# RF_INPUT.net
KiCad netlist of a schematic drawn in EAGLE
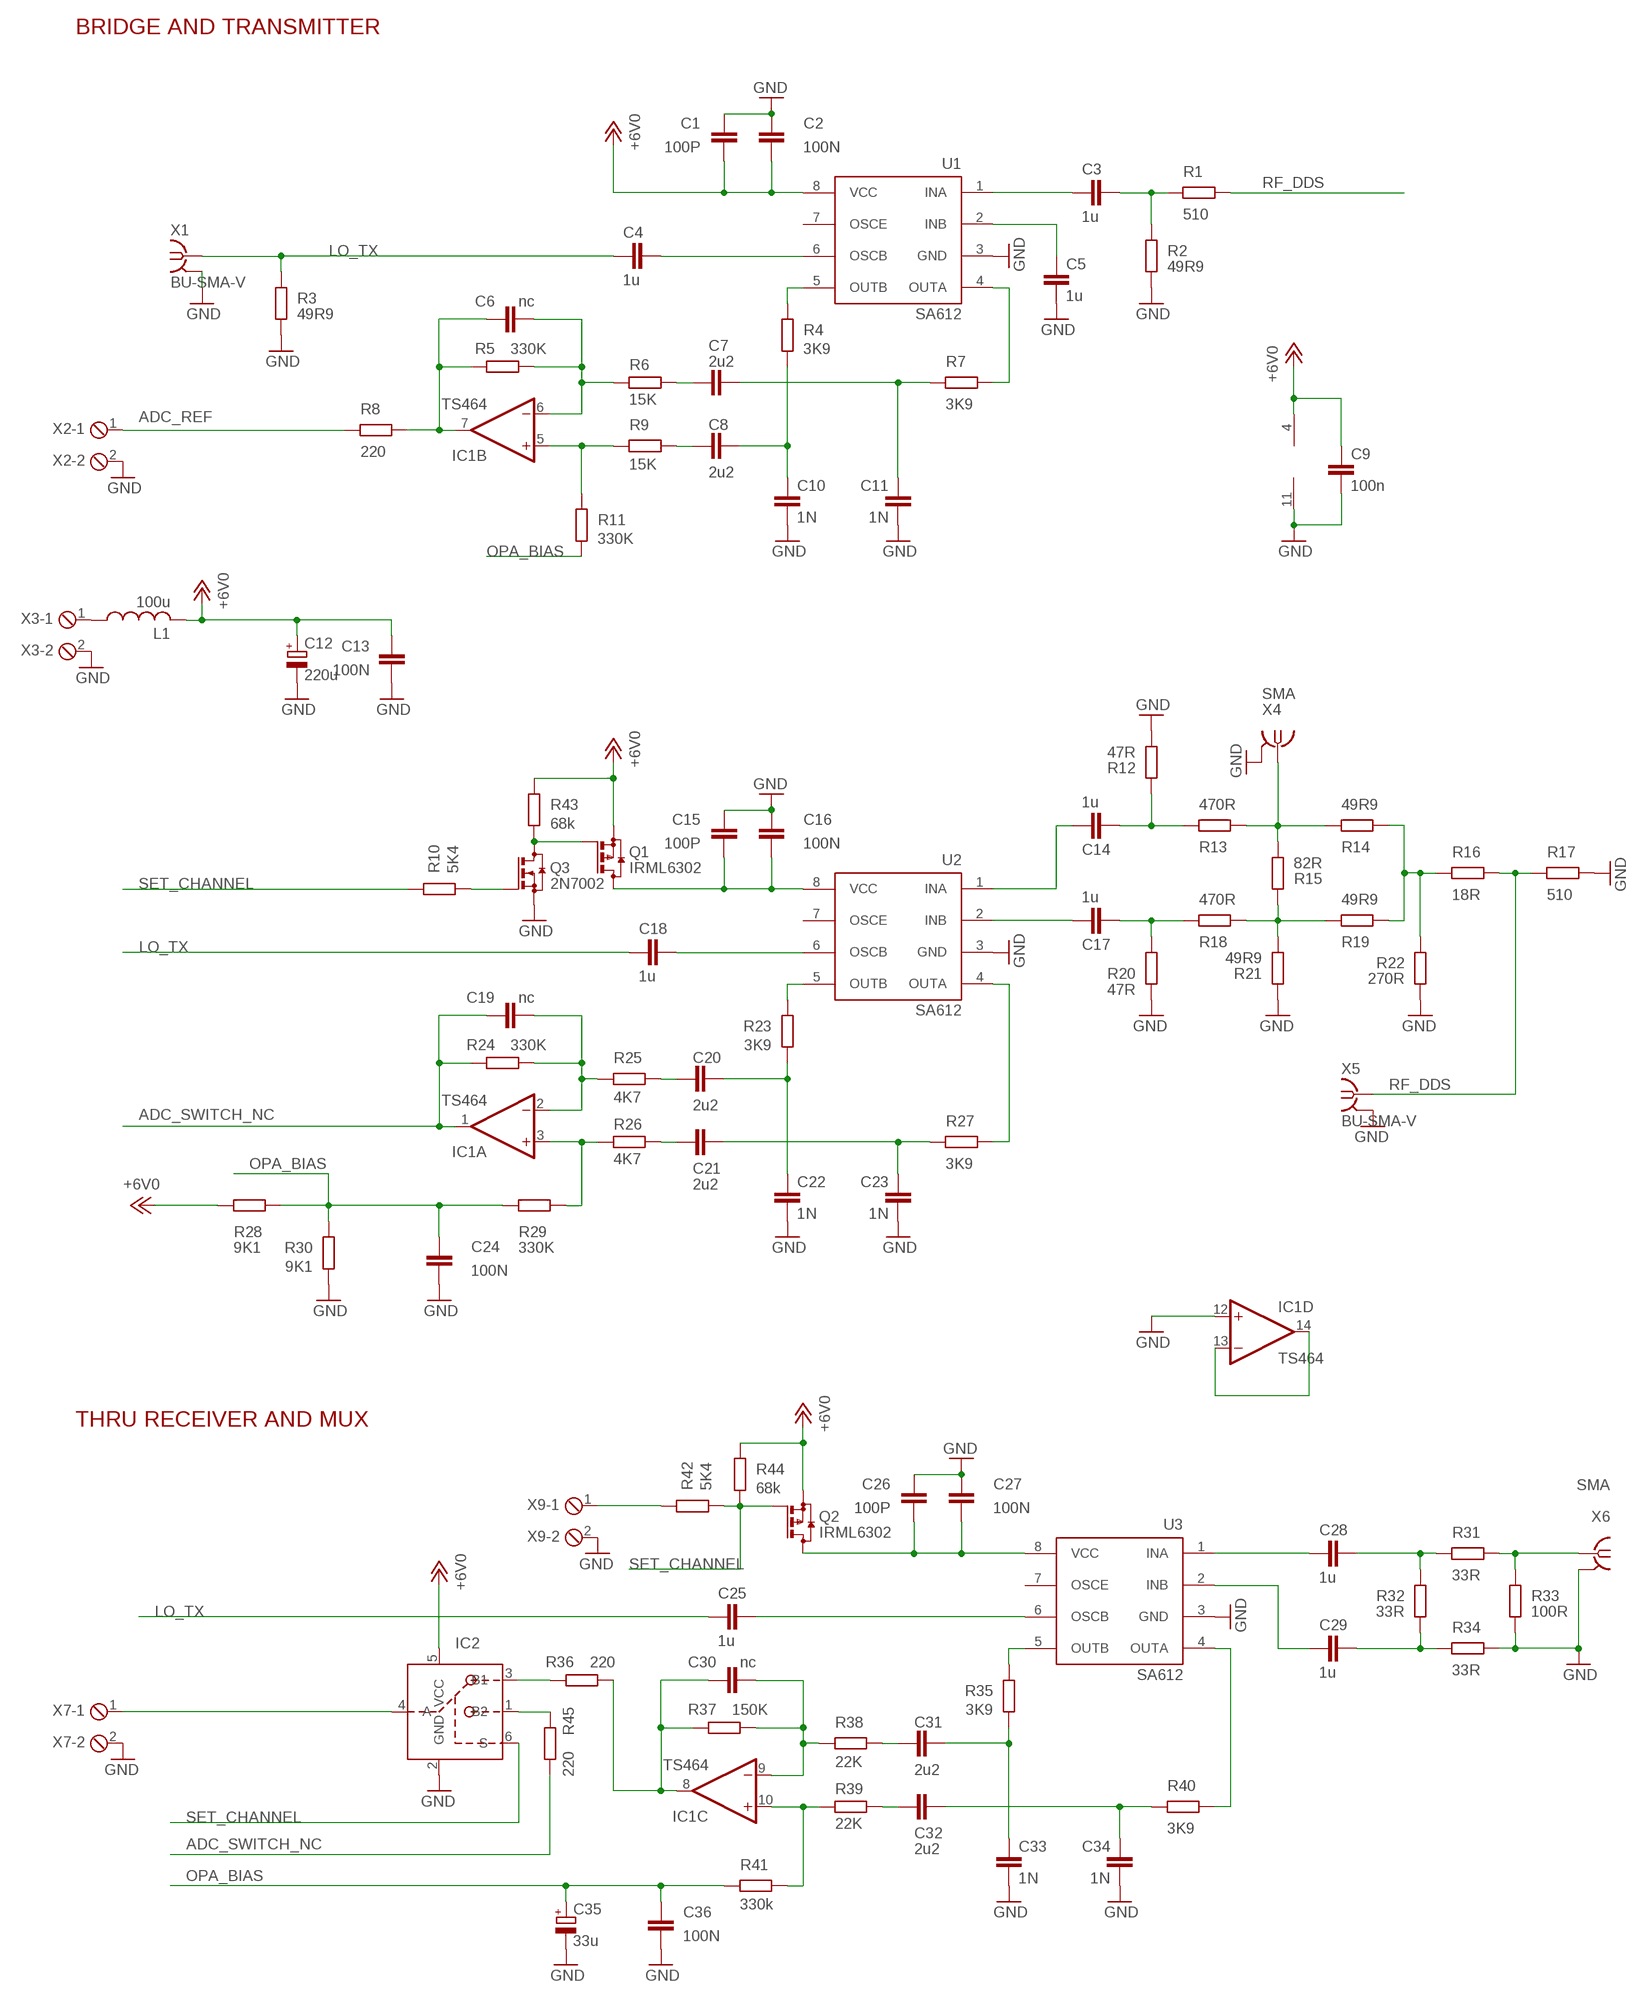
[diagram p0: schematic, sheet 1]

(export (version "E")
  (design (tool "Eeschema 10.0.6"))
  (components
    (comp (ref "C1")
      (value "100P")
      (footprint "eagle-import:C0805")
      (libsource (lib "eagle-import") (part "C-EUC0805"))
    )
    (comp (ref "C2")
      (value "100N")
      (footprint "eagle-import:C0603")
      (libsource (lib "eagle-import") (part "C-EUC0603"))
    )
    (comp (ref "C3")
      (value "1u")
      (footprint "eagle-import:C0603")
      (libsource (lib "eagle-import") (part "C-EUC0603"))
    )
    (comp (ref "C4")
      (value "1u")
      (footprint "eagle-import:C0805")
      (libsource (lib "eagle-import") (part "C-EUC0805"))
    )
    (comp (ref "C5")
      (value "1u")
      (footprint "eagle-import:C0603")
      (libsource (lib "eagle-import") (part "C-EUC0603"))
    )
    (comp (ref "C6")
      (value "nc")
      (footprint "eagle-import:C0805")
      (libsource (lib "eagle-import") (part "C-EUC0805"))
    )
    (comp (ref "C7")
      (value "2u2")
      (footprint "eagle-import:C0805")
      (libsource (lib "eagle-import") (part "C-EUC0805"))
    )
    (comp (ref "C8")
      (value "2u2")
      (footprint "eagle-import:C0805")
      (libsource (lib "eagle-import") (part "C-EUC0805"))
    )
    (comp (ref "C9")
      (value "100n")
      (footprint "eagle-import:C0603")
      (libsource (lib "eagle-import") (part "C-EUC0603"))
    )
    (comp (ref "C10")
      (value "1N")
      (footprint "eagle-import:C0805")
      (libsource (lib "eagle-import") (part "C-EUC0805"))
    )
    (comp (ref "C11")
      (value "1N")
      (footprint "eagle-import:C0805")
      (libsource (lib "eagle-import") (part "C-EUC0805"))
    )
    (comp (ref "C12")
      (value "220u")
      (footprint "eagle-import:153CLV-0605")
      (libsource (lib "eagle-import") (part "CPOL-EU153CLV-0605"))
    )
    (comp (ref "C13")
      (value "100N")
      (footprint "eagle-import:C0603")
      (libsource (lib "eagle-import") (part "C-EUC0603"))
    )
    (comp (ref "C14")
      (value "1u")
      (footprint "eagle-import:C0603")
      (libsource (lib "eagle-import") (part "C-EUC0603"))
    )
    (comp (ref "C15")
      (value "100P")
      (footprint "eagle-import:C0805")
      (libsource (lib "eagle-import") (part "C-EUC0805"))
    )
    (comp (ref "C16")
      (value "100N")
      (footprint "eagle-import:C0603")
      (libsource (lib "eagle-import") (part "C-EUC0603"))
    )
    (comp (ref "C17")
      (value "1u")
      (footprint "eagle-import:C0603")
      (libsource (lib "eagle-import") (part "C-EUC0603"))
    )
    (comp (ref "C18")
      (value "1u")
      (footprint "eagle-import:C0805")
      (libsource (lib "eagle-import") (part "C-EUC0805"))
    )
    (comp (ref "C19")
      (value "nc")
      (footprint "eagle-import:C0805")
      (libsource (lib "eagle-import") (part "C-EUC0805"))
    )
    (comp (ref "C20")
      (value "2u2")
      (footprint "eagle-import:C0805")
      (libsource (lib "eagle-import") (part "C-EUC0805"))
    )
    (comp (ref "C21")
      (value "2u2")
      (footprint "eagle-import:C0805")
      (libsource (lib "eagle-import") (part "C-EUC0805"))
    )
    (comp (ref "C22")
      (value "1N")
      (footprint "eagle-import:C0805")
      (libsource (lib "eagle-import") (part "C-EUC0805"))
    )
    (comp (ref "C23")
      (value "1N")
      (footprint "eagle-import:C0805")
      (libsource (lib "eagle-import") (part "C-EUC0805"))
    )
    (comp (ref "C24")
      (value "100N")
      (footprint "eagle-import:C0603")
      (libsource (lib "eagle-import") (part "C-EUC0603"))
    )
    (comp (ref "C25")
      (value "1u")
      (footprint "eagle-import:C0805")
      (libsource (lib "eagle-import") (part "C-EUC0805"))
    )
    (comp (ref "C26")
      (value "100P")
      (footprint "eagle-import:C0805")
      (libsource (lib "eagle-import") (part "C-EUC0805"))
    )
    (comp (ref "C27")
      (value "100N")
      (footprint "eagle-import:C0603")
      (libsource (lib "eagle-import") (part "C-EUC0603"))
    )
    (comp (ref "C28")
      (value "1u")
      (footprint "eagle-import:C0603")
      (libsource (lib "eagle-import") (part "C-EUC0603"))
    )
    (comp (ref "C29")
      (value "1u")
      (footprint "eagle-import:C0603")
      (libsource (lib "eagle-import") (part "C-EUC0603"))
    )
    (comp (ref "C30")
      (value "nc")
      (footprint "eagle-import:C0805")
      (libsource (lib "eagle-import") (part "C-EUC0805"))
    )
    (comp (ref "C31")
      (value "2u2")
      (footprint "eagle-import:C0805")
      (libsource (lib "eagle-import") (part "C-EUC0805"))
    )
    (comp (ref "C32")
      (value "2u2")
      (footprint "eagle-import:C0805")
      (libsource (lib "eagle-import") (part "C-EUC0805"))
    )
    (comp (ref "C33")
      (value "1N")
      (footprint "eagle-import:C0805")
      (libsource (lib "eagle-import") (part "C-EUC0805"))
    )
    (comp (ref "C34")
      (value "1N")
      (footprint "eagle-import:C0805")
      (libsource (lib "eagle-import") (part "C-EUC0805"))
    )
    (comp (ref "C35")
      (value "33u")
      (footprint "eagle-import:153CLV-0605")
      (libsource (lib "eagle-import") (part "CPOL-EU153CLV-0605"))
    )
    (comp (ref "C36")
      (value "100N")
      (footprint "eagle-import:C0603")
      (libsource (lib "eagle-import") (part "C-EUC0603"))
    )
    (comp (ref "IC1")
      (value "TS464")
      (footprint "eagle-import:SO14")
      (libsource (lib "eagle-import") (part "AD8684R"))
    )
    (comp (ref "IC2")
      (value "SN74LVC1G3157DBVR")
      (footprint "eagle-import:SOT23-6")
      (libsource (lib "eagle-import") (part "SN74LVC1G3157DBVR"))
    )
    (comp (ref "L1")
      (value "100u")
      (footprint "eagle-import:0207_12")
      (libsource (lib "eagle-import") (part "L-US0207/12"))
    )
    (comp (ref "Q1")
      (value "IRML6302")
      (footprint "eagle-import:SOT23")
      (libsource (lib "eagle-import") (part "BSS84"))
    )
    (comp (ref "Q2")
      (value "IRML6302")
      (footprint "eagle-import:SOT23")
      (libsource (lib "eagle-import") (part "BSS84"))
    )
    (comp (ref "Q3")
      (value "2N7002")
      (footprint "eagle-import:SOT23")
      (libsource (lib "eagle-import") (part "BSS123"))
    )
    (comp (ref "R1")
      (value "510")
      (footprint "eagle-import:R0603")
      (libsource (lib "eagle-import") (part "R-EU_R0603"))
    )
    (comp (ref "R2")
      (value "49R9")
      (footprint "eagle-import:R0805")
      (libsource (lib "eagle-import") (part "R-EU_R0805"))
    )
    (comp (ref "R3")
      (value "49R9")
      (footprint "eagle-import:R0805")
      (libsource (lib "eagle-import") (part "R-EU_R0805"))
    )
    (comp (ref "R4")
      (value "3K9")
      (footprint "eagle-import:R0603")
      (libsource (lib "eagle-import") (part "R-EU_R0603"))
    )
    (comp (ref "R5")
      (value "330K")
      (footprint "eagle-import:R0603")
      (libsource (lib "eagle-import") (part "R-EU_R0603"))
    )
    (comp (ref "R6")
      (value "15K")
      (footprint "eagle-import:R0603")
      (libsource (lib "eagle-import") (part "R-EU_R0603"))
    )
    (comp (ref "R7")
      (value "3K9")
      (footprint "eagle-import:R0603")
      (libsource (lib "eagle-import") (part "R-EU_R0603"))
    )
    (comp (ref "R8")
      (value "220")
      (footprint "eagle-import:R0603")
      (libsource (lib "eagle-import") (part "R-EU_R0603"))
    )
    (comp (ref "R9")
      (value "15K")
      (footprint "eagle-import:R0603")
      (libsource (lib "eagle-import") (part "R-EU_R0603"))
    )
    (comp (ref "R10")
      (value "5K4")
      (footprint "eagle-import:R0603")
      (libsource (lib "eagle-import") (part "R-EU_R0603"))
    )
    (comp (ref "R11")
      (value "330K")
      (footprint "eagle-import:R0603")
      (libsource (lib "eagle-import") (part "R-EU_R0603"))
    )
    (comp (ref "R12")
      (value "47R")
      (footprint "eagle-import:R0603")
      (libsource (lib "eagle-import") (part "R-EU_R0603"))
    )
    (comp (ref "R13")
      (value "470R")
      (footprint "eagle-import:R0603")
      (libsource (lib "eagle-import") (part "R-EU_R0603"))
    )
    (comp (ref "R14")
      (value "49R9")
      (footprint "eagle-import:R0805")
      (libsource (lib "eagle-import") (part "R-EU_R0805"))
    )
    (comp (ref "R15")
      (value "82R")
      (footprint "eagle-import:R0603")
      (libsource (lib "eagle-import") (part "R-EU_R0603"))
    )
    (comp (ref "R16")
      (value "18R")
      (footprint "eagle-import:R0603")
      (libsource (lib "eagle-import") (part "R-EU_R0603"))
    )
    (comp (ref "R17")
      (value "510")
      (footprint "eagle-import:R0603")
      (libsource (lib "eagle-import") (part "R-EU_R0603"))
    )
    (comp (ref "R18")
      (value "470R")
      (footprint "eagle-import:R0603")
      (libsource (lib "eagle-import") (part "R-EU_R0603"))
    )
    (comp (ref "R19")
      (value "49R9")
      (footprint "eagle-import:R0805")
      (libsource (lib "eagle-import") (part "R-EU_R0805"))
    )
    (comp (ref "R20")
      (value "47R")
      (footprint "eagle-import:R0603")
      (libsource (lib "eagle-import") (part "R-EU_R0603"))
    )
    (comp (ref "R21")
      (value "49R9")
      (footprint "eagle-import:R0805")
      (libsource (lib "eagle-import") (part "R-EU_R0805"))
    )
    (comp (ref "R22")
      (value "270R")
      (footprint "eagle-import:R0603")
      (libsource (lib "eagle-import") (part "R-EU_R0603"))
    )
    (comp (ref "R23")
      (value "3K9")
      (footprint "eagle-import:R0603")
      (libsource (lib "eagle-import") (part "R-EU_R0603"))
    )
    (comp (ref "R24")
      (value "330K")
      (footprint "eagle-import:R0603")
      (libsource (lib "eagle-import") (part "R-EU_R0603"))
    )
    (comp (ref "R25")
      (value "4K7")
      (footprint "eagle-import:R0603")
      (libsource (lib "eagle-import") (part "R-EU_R0603"))
    )
    (comp (ref "R26")
      (value "4K7")
      (footprint "eagle-import:R0603")
      (libsource (lib "eagle-import") (part "R-EU_R0603"))
    )
    (comp (ref "R27")
      (value "3K9")
      (footprint "eagle-import:R0603")
      (libsource (lib "eagle-import") (part "R-EU_R0603"))
    )
    (comp (ref "R28")
      (value "9K1")
      (footprint "eagle-import:R0603")
      (libsource (lib "eagle-import") (part "R-EU_R0603"))
    )
    (comp (ref "R29")
      (value "330K")
      (footprint "eagle-import:R0603")
      (libsource (lib "eagle-import") (part "R-EU_R0603"))
    )
    (comp (ref "R30")
      (value "9K1")
      (footprint "eagle-import:R0603")
      (libsource (lib "eagle-import") (part "R-EU_R0603"))
    )
    (comp (ref "R31")
      (value "33R")
      (footprint "eagle-import:R0603")
      (libsource (lib "eagle-import") (part "R-EU_R0603"))
    )
    (comp (ref "R32")
      (value "33R")
      (footprint "eagle-import:R0603")
      (libsource (lib "eagle-import") (part "R-EU_R0603"))
    )
    (comp (ref "R33")
      (value "100R")
      (footprint "eagle-import:R0603")
      (libsource (lib "eagle-import") (part "R-EU_R0603"))
    )
    (comp (ref "R34")
      (value "33R")
      (footprint "eagle-import:R0603")
      (libsource (lib "eagle-import") (part "R-EU_R0603"))
    )
    (comp (ref "R35")
      (value "3K9")
      (footprint "eagle-import:R0603")
      (libsource (lib "eagle-import") (part "R-EU_R0603"))
    )
    (comp (ref "R36")
      (value "220")
      (footprint "eagle-import:R0603")
      (libsource (lib "eagle-import") (part "R-EU_R0603"))
    )
    (comp (ref "R37")
      (value "150K")
      (footprint "eagle-import:R0603")
      (libsource (lib "eagle-import") (part "R-EU_R0603"))
    )
    (comp (ref "R38")
      (value "22K")
      (footprint "eagle-import:R0603")
      (libsource (lib "eagle-import") (part "R-EU_R0603"))
    )
    (comp (ref "R39")
      (value "22K")
      (footprint "eagle-import:R0603")
      (libsource (lib "eagle-import") (part "R-EU_R0603"))
    )
    (comp (ref "R40")
      (value "3K9")
      (footprint "eagle-import:R0603")
      (libsource (lib "eagle-import") (part "R-EU_R0603"))
    )
    (comp (ref "R41")
      (value "330k")
      (footprint "eagle-import:R0603")
      (libsource (lib "eagle-import") (part "R-EU_R0603"))
    )
    (comp (ref "R42")
      (value "5K4")
      (footprint "eagle-import:R0603")
      (libsource (lib "eagle-import") (part "R-EU_R0603"))
    )
    (comp (ref "R43")
      (value "68k")
      (footprint "eagle-import:R0603")
      (libsource (lib "eagle-import") (part "R-EU_R0603"))
    )
    (comp (ref "R44")
      (value "68k")
      (footprint "eagle-import:R0603")
      (libsource (lib "eagle-import") (part "R-EU_R0603"))
    )
    (comp (ref "R45")
      (value "220")
      (footprint "eagle-import:R0603")
      (libsource (lib "eagle-import") (part "R-EU_R0603"))
    )
    (comp (ref "U1")
      (value "SA612")
      (footprint "eagle-import:SO8")
      (libsource (lib "eagle-import") (part "SA612"))
    )
    (comp (ref "U2")
      (value "SA612")
      (footprint "eagle-import:SO8")
      (libsource (lib "eagle-import") (part "SA612"))
    )
    (comp (ref "U3")
      (value "SA612")
      (footprint "eagle-import:SO8")
      (libsource (lib "eagle-import") (part "SA612"))
    )
    (comp (ref "X1")
      (value "BU-SMA-V")
      (footprint "eagle-import:BU-SMA-V")
      (libsource (lib "eagle-import") (part "BU-SMA-V"))
    )
    (comp (ref "X2")
      (value "MPT2")
      (footprint "eagle-import:2POL254")
      (libsource (lib "eagle-import") (part "MPT2"))
    )
    (comp (ref "X3")
      (value "MPT2")
      (footprint "eagle-import:2POL254")
      (libsource (lib "eagle-import") (part "MPT2"))
    )
    (comp (ref "X4")
      (value "SMA")
      (footprint "eagle-import:J502-ND-142-0701-801_806")
      (fields (field (name "MF") "JOHNSON COMPONENTS") (field (name "MPN") "142-0701-801"))
      (libsource (lib "eagle-import") (part "SMA-142-0701-801/806"))
    )
    (comp (ref "X5")
      (value "BU-SMA-V")
      (footprint "eagle-import:BU-SMA-V")
      (libsource (lib "eagle-import") (part "BU-SMA-V"))
    )
    (comp (ref "X6")
      (value "SMA")
      (footprint "eagle-import:J502-ND-142-0701-801_806")
      (fields (field (name "MF") "JOHNSON COMPONENTS") (field (name "MPN") "142-0701-801"))
      (libsource (lib "eagle-import") (part "SMA-142-0701-801/806"))
    )
    (comp (ref "X7")
      (value "MPT2")
      (footprint "eagle-import:2POL254")
      (libsource (lib "eagle-import") (part "MPT2"))
    )
    (comp (ref "X9")
      (value "MPT2")
      (footprint "eagle-import:2POL254")
      (libsource (lib "eagle-import") (part "MPT2"))
    )
  )
  (nets
    (net (code "1") (name "+6V0") (class "Default")
      (node (ref "C1") (pin "1") (pinfunction "1_1") (pintype "passive"))
      (node (ref "C12") (pin "+") (pinfunction "+_+") (pintype "passive"))
      (node (ref "C13") (pin "1") (pinfunction "1_1") (pintype "passive"))
      (node (ref "C2") (pin "1") (pinfunction "1_1") (pintype "passive"))
      (node (ref "C9") (pin "1") (pinfunction "1_1") (pintype "passive"))
      (node (ref "IC1") (pin "4") (pinfunction "V+_4") (pintype "power_in"))
      (node (ref "IC2") (pin "5") (pinfunction "VCC_5") (pintype "power_in"))
      (node (ref "L1") (pin "2") (pinfunction "2_2") (pintype "passive"))
      (node (ref "Q1") (pin "2") (pinfunction "S_2") (pintype "passive"))
      (node (ref "Q2") (pin "2") (pinfunction "S_2") (pintype "passive"))
      (node (ref "R28") (pin "2") (pinfunction "2_2") (pintype "passive"))
      (node (ref "R43") (pin "1") (pinfunction "1_1") (pintype "passive"))
      (node (ref "R44") (pin "1") (pinfunction "1_1") (pintype "passive"))
      (node (ref "U1") (pin "8") (pinfunction "VCC_8") (pintype "bidirectional"))
    )
    (net (code "2") (name "/ADC_REF") (class "Default")
      (node (ref "R8") (pin "1") (pinfunction "1_1") (pintype "passive"))
      (node (ref "X2") (pin "1") (pinfunction "1_1") (pintype "passive"))
    )
    (net (code "3") (name "/ADC_SWITCH_NC") (class "Default")
      (node (ref "C19") (pin "1") (pinfunction "1_1") (pintype "passive"))
      (node (ref "IC1") (pin "1") (pinfunction "OUT_1") (pintype "output"))
      (node (ref "R24") (pin "2") (pinfunction "2_2") (pintype "passive"))
      (node (ref "R45") (pin "1") (pinfunction "1_1") (pintype "passive"))
    )
    (net (code "4") (name "/LO_TX") (class "Default")
      (node (ref "C18") (pin "1") (pinfunction "1_1") (pintype "passive"))
      (node (ref "C25") (pin "1") (pinfunction "1_1") (pintype "passive"))
      (node (ref "C4") (pin "1") (pinfunction "1_1") (pintype "passive"))
      (node (ref "R3") (pin "1") (pinfunction "1_1") (pintype "passive"))
      (node (ref "X1") (pin "1") (pinfunction "1_1") (pintype "passive"))
    )
    (net (code "5") (name "/OPA_BIAS") (class "Default")
      (node (ref "C24") (pin "2") (pinfunction "2_2") (pintype "passive"))
      (node (ref "C35") (pin "+") (pinfunction "+_+") (pintype "passive"))
      (node (ref "C36") (pin "1") (pinfunction "1_1") (pintype "passive"))
      (node (ref "R11") (pin "2") (pinfunction "2_2") (pintype "passive"))
      (node (ref "R28") (pin "1") (pinfunction "1_1") (pintype "passive"))
      (node (ref "R29") (pin "2") (pinfunction "2_2") (pintype "passive"))
      (node (ref "R30") (pin "1") (pinfunction "1_1") (pintype "passive"))
      (node (ref "R41") (pin "2") (pinfunction "2_2") (pintype "passive"))
    )
    (net (code "6") (name "/RF_DDS") (class "Default")
      (node (ref "R1") (pin "1") (pinfunction "1_1") (pintype "passive"))
      (node (ref "R16") (pin "1") (pinfunction "1_1") (pintype "passive"))
      (node (ref "R17") (pin "1") (pinfunction "1_1") (pintype "passive"))
      (node (ref "X5") (pin "1") (pinfunction "1_1") (pintype "passive"))
    )
    (net (code "7") (name "/SET_CHANNEL") (class "Default")
      (node (ref "IC2") (pin "6") (pinfunction "S_6") (pintype "bidirectional"))
      (node (ref "Q2") (pin "1") (pinfunction "G_1") (pintype "passive"))
      (node (ref "R10") (pin "1") (pinfunction "1_1") (pintype "passive"))
      (node (ref "R42") (pin "2") (pinfunction "2_2") (pintype "passive"))
      (node (ref "R44") (pin "2") (pinfunction "2_2") (pintype "passive"))
    )
    (net (code "8") (name "GND") (class "Default")
      (node (ref "C1") (pin "2") (pinfunction "2_2") (pintype "passive"))
      (node (ref "C10") (pin "2") (pinfunction "2_2") (pintype "passive"))
      (node (ref "C11") (pin "2") (pinfunction "2_2") (pintype "passive"))
      (node (ref "C12") (pin "-") (pinfunction "-_-") (pintype "passive"))
      (node (ref "C13") (pin "2") (pinfunction "2_2") (pintype "passive"))
      (node (ref "C15") (pin "2") (pinfunction "2_2") (pintype "passive"))
      (node (ref "C16") (pin "2") (pinfunction "2_2") (pintype "passive"))
      (node (ref "C2") (pin "2") (pinfunction "2_2") (pintype "passive"))
      (node (ref "C22") (pin "2") (pinfunction "2_2") (pintype "passive"))
      (node (ref "C23") (pin "2") (pinfunction "2_2") (pintype "passive"))
      (node (ref "C24") (pin "1") (pinfunction "1_1") (pintype "passive"))
      (node (ref "C26") (pin "2") (pinfunction "2_2") (pintype "passive"))
      (node (ref "C27") (pin "2") (pinfunction "2_2") (pintype "passive"))
      (node (ref "C33") (pin "2") (pinfunction "2_2") (pintype "passive"))
      (node (ref "C34") (pin "2") (pinfunction "2_2") (pintype "passive"))
      (node (ref "C35") (pin "-") (pinfunction "-_-") (pintype "passive"))
      (node (ref "C36") (pin "2") (pinfunction "2_2") (pintype "passive"))
      (node (ref "C5") (pin "2") (pinfunction "2_2") (pintype "passive"))
      (node (ref "C9") (pin "2") (pinfunction "2_2") (pintype "passive"))
      (node (ref "IC1") (pin "11") (pinfunction "V-_11") (pintype "power_in"))
      (node (ref "IC1") (pin "12") (pinfunction "+IN_12") (pintype "input"))
      (node (ref "IC2") (pin "2") (pinfunction "GND_2") (pintype "power_in"))
      (node (ref "Q3") (pin "2") (pinfunction "S_2") (pintype "passive"))
      (node (ref "R12") (pin "2") (pinfunction "2_2") (pintype "passive"))
      (node (ref "R17") (pin "2") (pinfunction "2_2") (pintype "passive"))
      (node (ref "R2") (pin "1") (pinfunction "1_1") (pintype "passive"))
      (node (ref "R20") (pin "1") (pinfunction "1_1") (pintype "passive"))
      (node (ref "R21") (pin "1") (pinfunction "1_1") (pintype "passive"))
      (node (ref "R22") (pin "2") (pinfunction "2_2") (pintype "passive"))
      (node (ref "R3") (pin "2") (pinfunction "2_2") (pintype "passive"))
      (node (ref "R30") (pin "2") (pinfunction "2_2") (pintype "passive"))
      (node (ref "R33") (pin "2") (pinfunction "2_2") (pintype "passive"))
      (node (ref "R34") (pin "1") (pinfunction "1_1") (pintype "passive"))
      (node (ref "U1") (pin "3") (pinfunction "GND_3") (pintype "bidirectional"))
      (node (ref "U2") (pin "3") (pinfunction "GND_3") (pintype "bidirectional"))
      (node (ref "U3") (pin "3") (pinfunction "GND_3") (pintype "bidirectional"))
      (node (ref "X1") (pin "2") (pinfunction "2_2") (pintype "passive"))
      (node (ref "X1") (pin "3") (pinfunction "2_3") (pintype "passive"))
      (node (ref "X1") (pin "4") (pinfunction "2_4") (pintype "passive"))
      (node (ref "X1") (pin "5") (pinfunction "2_5") (pintype "passive"))
      (node (ref "X2") (pin "2") (pinfunction "1_2") (pintype "passive"))
      (node (ref "X3") (pin "2") (pinfunction "1_2") (pintype "passive"))
      (node (ref "X4") (pin "G@1") (pinfunction "2_G@1") (pintype "passive"))
      (node (ref "X4") (pin "G@2") (pinfunction "2_G@2") (pintype "passive"))
      (node (ref "X4") (pin "G@3") (pinfunction "2_G@3") (pintype "passive"))
      (node (ref "X4") (pin "G@4") (pinfunction "2_G@4") (pintype "passive"))
      (node (ref "X5") (pin "2") (pinfunction "2_2") (pintype "passive"))
      (node (ref "X5") (pin "3") (pinfunction "2_3") (pintype "passive"))
      (node (ref "X5") (pin "4") (pinfunction "2_4") (pintype "passive"))
      (node (ref "X5") (pin "5") (pinfunction "2_5") (pintype "passive"))
      (node (ref "X6") (pin "G@1") (pinfunction "2_G@1") (pintype "passive"))
      (node (ref "X6") (pin "G@2") (pinfunction "2_G@2") (pintype "passive"))
      (node (ref "X6") (pin "G@3") (pinfunction "2_G@3") (pintype "passive"))
      (node (ref "X6") (pin "G@4") (pinfunction "2_G@4") (pintype "passive"))
      (node (ref "X7") (pin "2") (pinfunction "1_2") (pintype "passive"))
      (node (ref "X9") (pin "2") (pinfunction "1_2") (pintype "passive"))
    )
    (net (code "9") (name "Net-(C3-Pad2)") (class "Default")
      (node (ref "C3") (pin "2") (pinfunction "2_2") (pintype "passive"))
      (node (ref "R1") (pin "2") (pinfunction "2_2") (pintype "passive"))
      (node (ref "R2") (pin "2") (pinfunction "2_2") (pintype "passive"))
    )
    (net (code "10") (name "Net-(C7-Pad1)") (class "Default")
      (node (ref "C7") (pin "1") (pinfunction "1_1") (pintype "passive"))
      (node (ref "R6") (pin "1") (pinfunction "1_1") (pintype "passive"))
    )
    (net (code "11") (name "Net-(C8-Pad1)") (class "Default")
      (node (ref "C8") (pin "1") (pinfunction "1_1") (pintype "passive"))
      (node (ref "R9") (pin "1") (pinfunction "1_1") (pintype "passive"))
    )
    (net (code "12") (name "Net-(C10-Pad1)") (class "Default")
      (node (ref "C10") (pin "1") (pinfunction "1_1") (pintype "passive"))
      (node (ref "C8") (pin "2") (pinfunction "2_2") (pintype "passive"))
      (node (ref "R4") (pin "2") (pinfunction "2_2") (pintype "passive"))
    )
    (net (code "13") (name "Net-(C11-Pad1)") (class "Default")
      (node (ref "C11") (pin "1") (pinfunction "1_1") (pintype "passive"))
      (node (ref "C7") (pin "2") (pinfunction "2_2") (pintype "passive"))
      (node (ref "R7") (pin "2") (pinfunction "2_2") (pintype "passive"))
    )
    (net (code "14") (name "Net-(C14-Pad2)") (class "Default")
      (node (ref "C14") (pin "2") (pinfunction "2_2") (pintype "passive"))
      (node (ref "R12") (pin "1") (pinfunction "1_1") (pintype "passive"))
      (node (ref "R13") (pin "2") (pinfunction "2_2") (pintype "passive"))
    )
    (net (code "15") (name "Net-(C17-Pad2)") (class "Default")
      (node (ref "C17") (pin "2") (pinfunction "2_2") (pintype "passive"))
      (node (ref "R18") (pin "2") (pinfunction "2_2") (pintype "passive"))
      (node (ref "R20") (pin "2") (pinfunction "2_2") (pintype "passive"))
    )
    (net (code "16") (name "Net-(C20-Pad1)") (class "Default")
      (node (ref "C20") (pin "1") (pinfunction "1_1") (pintype "passive"))
      (node (ref "R25") (pin "1") (pinfunction "1_1") (pintype "passive"))
    )
    (net (code "17") (name "Net-(C20-Pad2)") (class "Default")
      (node (ref "C20") (pin "2") (pinfunction "2_2") (pintype "passive"))
      (node (ref "C22") (pin "1") (pinfunction "1_1") (pintype "passive"))
      (node (ref "R23") (pin "2") (pinfunction "2_2") (pintype "passive"))
    )
    (net (code "18") (name "Net-(C21-Pad1)") (class "Default")
      (node (ref "C21") (pin "1") (pinfunction "1_1") (pintype "passive"))
      (node (ref "R26") (pin "1") (pinfunction "1_1") (pintype "passive"))
    )
    (net (code "19") (name "Net-(C21-Pad2)") (class "Default")
      (node (ref "C21") (pin "2") (pinfunction "2_2") (pintype "passive"))
      (node (ref "C23") (pin "1") (pinfunction "1_1") (pintype "passive"))
      (node (ref "R27") (pin "2") (pinfunction "2_2") (pintype "passive"))
    )
    (net (code "20") (name "Net-(C28-Pad2)") (class "Default")
      (node (ref "C28") (pin "2") (pinfunction "2_2") (pintype "passive"))
      (node (ref "R31") (pin "2") (pinfunction "2_2") (pintype "passive"))
      (node (ref "R32") (pin "1") (pinfunction "1_1") (pintype "passive"))
    )
    (net (code "21") (name "Net-(C29-Pad2)") (class "Default")
      (node (ref "C29") (pin "2") (pinfunction "2_2") (pintype "passive"))
      (node (ref "R32") (pin "2") (pinfunction "2_2") (pintype "passive"))
      (node (ref "R34") (pin "2") (pinfunction "2_2") (pintype "passive"))
    )
    (net (code "22") (name "Net-(C31-Pad1)") (class "Default")
      (node (ref "C31") (pin "1") (pinfunction "1_1") (pintype "passive"))
      (node (ref "R38") (pin "1") (pinfunction "1_1") (pintype "passive"))
    )
    (net (code "23") (name "Net-(C31-Pad2)") (class "Default")
      (node (ref "C31") (pin "2") (pinfunction "2_2") (pintype "passive"))
      (node (ref "C33") (pin "1") (pinfunction "1_1") (pintype "passive"))
      (node (ref "R35") (pin "2") (pinfunction "2_2") (pintype "passive"))
    )
    (net (code "24") (name "Net-(C32-Pad1)") (class "Default")
      (node (ref "C32") (pin "1") (pinfunction "1_1") (pintype "passive"))
      (node (ref "R39") (pin "1") (pinfunction "1_1") (pintype "passive"))
    )
    (net (code "25") (name "Net-(C32-Pad2)") (class "Default")
      (node (ref "C32") (pin "2") (pinfunction "2_2") (pintype "passive"))
      (node (ref "C34") (pin "1") (pinfunction "1_1") (pintype "passive"))
      (node (ref "R40") (pin "2") (pinfunction "2_2") (pintype "passive"))
    )
    (net (code "26") (name "Net-(IC1A-+IN)") (class "Default")
      (node (ref "IC1") (pin "3") (pinfunction "+IN_3") (pintype "input"))
      (node (ref "R26") (pin "2") (pinfunction "2_2") (pintype "passive"))
      (node (ref "R29") (pin "1") (pinfunction "1_1") (pintype "passive"))
    )
    (net (code "27") (name "Net-(IC1A--IN)") (class "Default")
      (node (ref "C19") (pin "2") (pinfunction "2_2") (pintype "passive"))
      (node (ref "IC1") (pin "2") (pinfunction "-IN_2") (pintype "input"))
      (node (ref "R24") (pin "1") (pinfunction "1_1") (pintype "passive"))
      (node (ref "R25") (pin "2") (pinfunction "2_2") (pintype "passive"))
    )
    (net (code "28") (name "Net-(IC1B-+IN)") (class "Default")
      (node (ref "IC1") (pin "5") (pinfunction "+IN_5") (pintype "input"))
      (node (ref "R11") (pin "1") (pinfunction "1_1") (pintype "passive"))
      (node (ref "R9") (pin "2") (pinfunction "2_2") (pintype "passive"))
    )
    (net (code "29") (name "Net-(IC1B--IN)") (class "Default")
      (node (ref "C6") (pin "2") (pinfunction "2_2") (pintype "passive"))
      (node (ref "IC1") (pin "6") (pinfunction "-IN_6") (pintype "input"))
      (node (ref "R5") (pin "1") (pinfunction "1_1") (pintype "passive"))
      (node (ref "R6") (pin "2") (pinfunction "2_2") (pintype "passive"))
    )
    (net (code "30") (name "Net-(IC1B-OUT)") (class "Default")
      (node (ref "C6") (pin "1") (pinfunction "1_1") (pintype "passive"))
      (node (ref "IC1") (pin "7") (pinfunction "OUT_7") (pintype "output"))
      (node (ref "R5") (pin "2") (pinfunction "2_2") (pintype "passive"))
      (node (ref "R8") (pin "2") (pinfunction "2_2") (pintype "passive"))
    )
    (net (code "31") (name "Net-(IC1C-+IN)") (class "Default")
      (node (ref "IC1") (pin "10") (pinfunction "+IN_10") (pintype "input"))
      (node (ref "R39") (pin "2") (pinfunction "2_2") (pintype "passive"))
      (node (ref "R41") (pin "1") (pinfunction "1_1") (pintype "passive"))
    )
    (net (code "32") (name "Net-(IC1C--IN)") (class "Default")
      (node (ref "C30") (pin "2") (pinfunction "2_2") (pintype "passive"))
      (node (ref "IC1") (pin "9") (pinfunction "-IN_9") (pintype "input"))
      (node (ref "R37") (pin "1") (pinfunction "1_1") (pintype "passive"))
      (node (ref "R38") (pin "2") (pinfunction "2_2") (pintype "passive"))
    )
    (net (code "33") (name "Net-(IC1C-OUT)") (class "Default")
      (node (ref "C30") (pin "1") (pinfunction "1_1") (pintype "passive"))
      (node (ref "IC1") (pin "8") (pinfunction "OUT_8") (pintype "output"))
      (node (ref "R36") (pin "1") (pinfunction "1_1") (pintype "passive"))
      (node (ref "R37") (pin "2") (pinfunction "2_2") (pintype "passive"))
    )
    (net (code "34") (name "Net-(IC1D--IN)") (class "Default")
      (node (ref "IC1") (pin "13") (pinfunction "-IN_13") (pintype "input"))
      (node (ref "IC1") (pin "14") (pinfunction "OUT_14") (pintype "output"))
    )
    (net (code "35") (name "Net-(IC2-A)") (class "Default")
      (node (ref "IC2") (pin "4") (pinfunction "A_4") (pintype "bidirectional"))
      (node (ref "X7") (pin "1") (pinfunction "1_1") (pintype "passive"))
    )
    (net (code "36") (name "Net-(IC2-B1)") (class "Default")
      (node (ref "IC2") (pin "3") (pinfunction "B1_3") (pintype "bidirectional"))
      (node (ref "R36") (pin "2") (pinfunction "2_2") (pintype "passive"))
    )
    (net (code "37") (name "Net-(IC2-B2)") (class "Default")
      (node (ref "IC2") (pin "1") (pinfunction "B2_1") (pintype "bidirectional"))
      (node (ref "R45") (pin "2") (pinfunction "2_2") (pintype "passive"))
    )
    (net (code "38") (name "Net-(L1-Pad1)") (class "Default")
      (node (ref "L1") (pin "1") (pinfunction "1_1") (pintype "passive"))
      (node (ref "X3") (pin "1") (pinfunction "1_1") (pintype "passive"))
    )
    (net (code "39") (name "Net-(Q1-D)") (class "Default")
      (node (ref "C15") (pin "1") (pinfunction "1_1") (pintype "passive"))
      (node (ref "C16") (pin "1") (pinfunction "1_1") (pintype "passive"))
      (node (ref "Q1") (pin "3") (pinfunction "D_3") (pintype "passive"))
      (node (ref "U2") (pin "8") (pinfunction "VCC_8") (pintype "bidirectional"))
    )
    (net (code "40") (name "Net-(Q1-G)") (class "Default")
      (node (ref "Q1") (pin "1") (pinfunction "G_1") (pintype "passive"))
      (node (ref "Q3") (pin "3") (pinfunction "D_3") (pintype "passive"))
      (node (ref "R43") (pin "2") (pinfunction "2_2") (pintype "passive"))
    )
    (net (code "41") (name "Net-(Q2-D)") (class "Default")
      (node (ref "C26") (pin "1") (pinfunction "1_1") (pintype "passive"))
      (node (ref "C27") (pin "1") (pinfunction "1_1") (pintype "passive"))
      (node (ref "Q2") (pin "3") (pinfunction "D_3") (pintype "passive"))
      (node (ref "U3") (pin "8") (pinfunction "VCC_8") (pintype "bidirectional"))
    )
    (net (code "42") (name "Net-(Q3-G)") (class "Default")
      (node (ref "Q3") (pin "1") (pinfunction "G_1") (pintype "passive"))
      (node (ref "R10") (pin "2") (pinfunction "2_2") (pintype "passive"))
    )
    (net (code "43") (name "Net-(R13-Pad1)") (class "Default")
      (node (ref "R13") (pin "1") (pinfunction "1_1") (pintype "passive"))
      (node (ref "R14") (pin "2") (pinfunction "2_2") (pintype "passive"))
      (node (ref "R15") (pin "2") (pinfunction "2_2") (pintype "passive"))
      (node (ref "X4") (pin "1") (pinfunction "1_1") (pintype "passive"))
    )
    (net (code "44") (name "Net-(R14-Pad1)") (class "Default")
      (node (ref "R14") (pin "1") (pinfunction "1_1") (pintype "passive"))
      (node (ref "R16") (pin "2") (pinfunction "2_2") (pintype "passive"))
      (node (ref "R19") (pin "1") (pinfunction "1_1") (pintype "passive"))
      (node (ref "R22") (pin "1") (pinfunction "1_1") (pintype "passive"))
    )
    (net (code "45") (name "Net-(R15-Pad1)") (class "Default")
      (node (ref "R15") (pin "1") (pinfunction "1_1") (pintype "passive"))
      (node (ref "R18") (pin "1") (pinfunction "1_1") (pintype "passive"))
      (node (ref "R19") (pin "2") (pinfunction "2_2") (pintype "passive"))
      (node (ref "R21") (pin "2") (pinfunction "2_2") (pintype "passive"))
    )
    (net (code "46") (name "Net-(R31-Pad1)") (class "Default")
      (node (ref "R31") (pin "1") (pinfunction "1_1") (pintype "passive"))
      (node (ref "R33") (pin "1") (pinfunction "1_1") (pintype "passive"))
      (node (ref "X6") (pin "1") (pinfunction "1_1") (pintype "passive"))
    )
    (net (code "47") (name "Net-(R42-Pad1)") (class "Default")
      (node (ref "R42") (pin "1") (pinfunction "1_1") (pintype "passive"))
      (node (ref "X9") (pin "1") (pinfunction "1_1") (pintype "passive"))
    )
    (net (code "48") (name "Net-(U1-INA)") (class "Default")
      (node (ref "C3") (pin "1") (pinfunction "1_1") (pintype "passive"))
      (node (ref "U1") (pin "1") (pinfunction "INA_1") (pintype "bidirectional"))
    )
    (net (code "49") (name "Net-(U1-INB)") (class "Default")
      (node (ref "C5") (pin "1") (pinfunction "1_1") (pintype "passive"))
      (node (ref "U1") (pin "2") (pinfunction "INB_2") (pintype "bidirectional"))
    )
    (net (code "50") (name "Net-(U1-OSCB)") (class "Default")
      (node (ref "C4") (pin "2") (pinfunction "2_2") (pintype "passive"))
      (node (ref "U1") (pin "6") (pinfunction "OSCB_6") (pintype "bidirectional"))
    )
    (net (code "51") (name "Net-(U1-OUTA)") (class "Default")
      (node (ref "R7") (pin "1") (pinfunction "1_1") (pintype "passive"))
      (node (ref "U1") (pin "4") (pinfunction "OUTA_4") (pintype "bidirectional"))
    )
    (net (code "52") (name "Net-(U1-OUTB)") (class "Default")
      (node (ref "R4") (pin "1") (pinfunction "1_1") (pintype "passive"))
      (node (ref "U1") (pin "5") (pinfunction "OUTB_5") (pintype "bidirectional"))
    )
    (net (code "53") (name "Net-(U2-INA)") (class "Default")
      (node (ref "C14") (pin "1") (pinfunction "1_1") (pintype "passive"))
      (node (ref "U2") (pin "1") (pinfunction "INA_1") (pintype "bidirectional"))
    )
    (net (code "54") (name "Net-(U2-INB)") (class "Default")
      (node (ref "C17") (pin "1") (pinfunction "1_1") (pintype "passive"))
      (node (ref "U2") (pin "2") (pinfunction "INB_2") (pintype "bidirectional"))
    )
    (net (code "55") (name "Net-(U2-OSCB)") (class "Default")
      (node (ref "C18") (pin "2") (pinfunction "2_2") (pintype "passive"))
      (node (ref "U2") (pin "6") (pinfunction "OSCB_6") (pintype "bidirectional"))
    )
    (net (code "56") (name "Net-(U2-OUTA)") (class "Default")
      (node (ref "R27") (pin "1") (pinfunction "1_1") (pintype "passive"))
      (node (ref "U2") (pin "4") (pinfunction "OUTA_4") (pintype "bidirectional"))
    )
    (net (code "57") (name "Net-(U2-OUTB)") (class "Default")
      (node (ref "R23") (pin "1") (pinfunction "1_1") (pintype "passive"))
      (node (ref "U2") (pin "5") (pinfunction "OUTB_5") (pintype "bidirectional"))
    )
    (net (code "58") (name "Net-(U3-INA)") (class "Default")
      (node (ref "C28") (pin "1") (pinfunction "1_1") (pintype "passive"))
      (node (ref "U3") (pin "1") (pinfunction "INA_1") (pintype "bidirectional"))
    )
    (net (code "59") (name "Net-(U3-INB)") (class "Default")
      (node (ref "C29") (pin "1") (pinfunction "1_1") (pintype "passive"))
      (node (ref "U3") (pin "2") (pinfunction "INB_2") (pintype "bidirectional"))
    )
    (net (code "60") (name "Net-(U3-OSCB)") (class "Default")
      (node (ref "C25") (pin "2") (pinfunction "2_2") (pintype "passive"))
      (node (ref "U3") (pin "6") (pinfunction "OSCB_6") (pintype "bidirectional"))
    )
    (net (code "61") (name "Net-(U3-OUTA)") (class "Default")
      (node (ref "R40") (pin "1") (pinfunction "1_1") (pintype "passive"))
      (node (ref "U3") (pin "4") (pinfunction "OUTA_4") (pintype "bidirectional"))
    )
    (net (code "62") (name "Net-(U3-OUTB)") (class "Default")
      (node (ref "R35") (pin "1") (pinfunction "1_1") (pintype "passive"))
      (node (ref "U3") (pin "5") (pinfunction "OUTB_5") (pintype "bidirectional"))
    )
    (net (code "63") (name "unconnected-(U1-OSCE-Pad7)") (class "Default")
      (node (ref "U1") (pin "7") (pinfunction "OSCE_7") (pintype "bidirectional"))
    )
    (net (code "64") (name "unconnected-(U2-OSCE-Pad7)") (class "Default")
      (node (ref "U2") (pin "7") (pinfunction "OSCE_7") (pintype "bidirectional"))
    )
    (net (code "65") (name "unconnected-(U3-OSCE-Pad7)") (class "Default")
      (node (ref "U3") (pin "7") (pinfunction "OSCE_7") (pintype "bidirectional"))
    )
  )
)
